# sbus-ppm.net
KiCad netlist of a schematic drawn in EAGLE
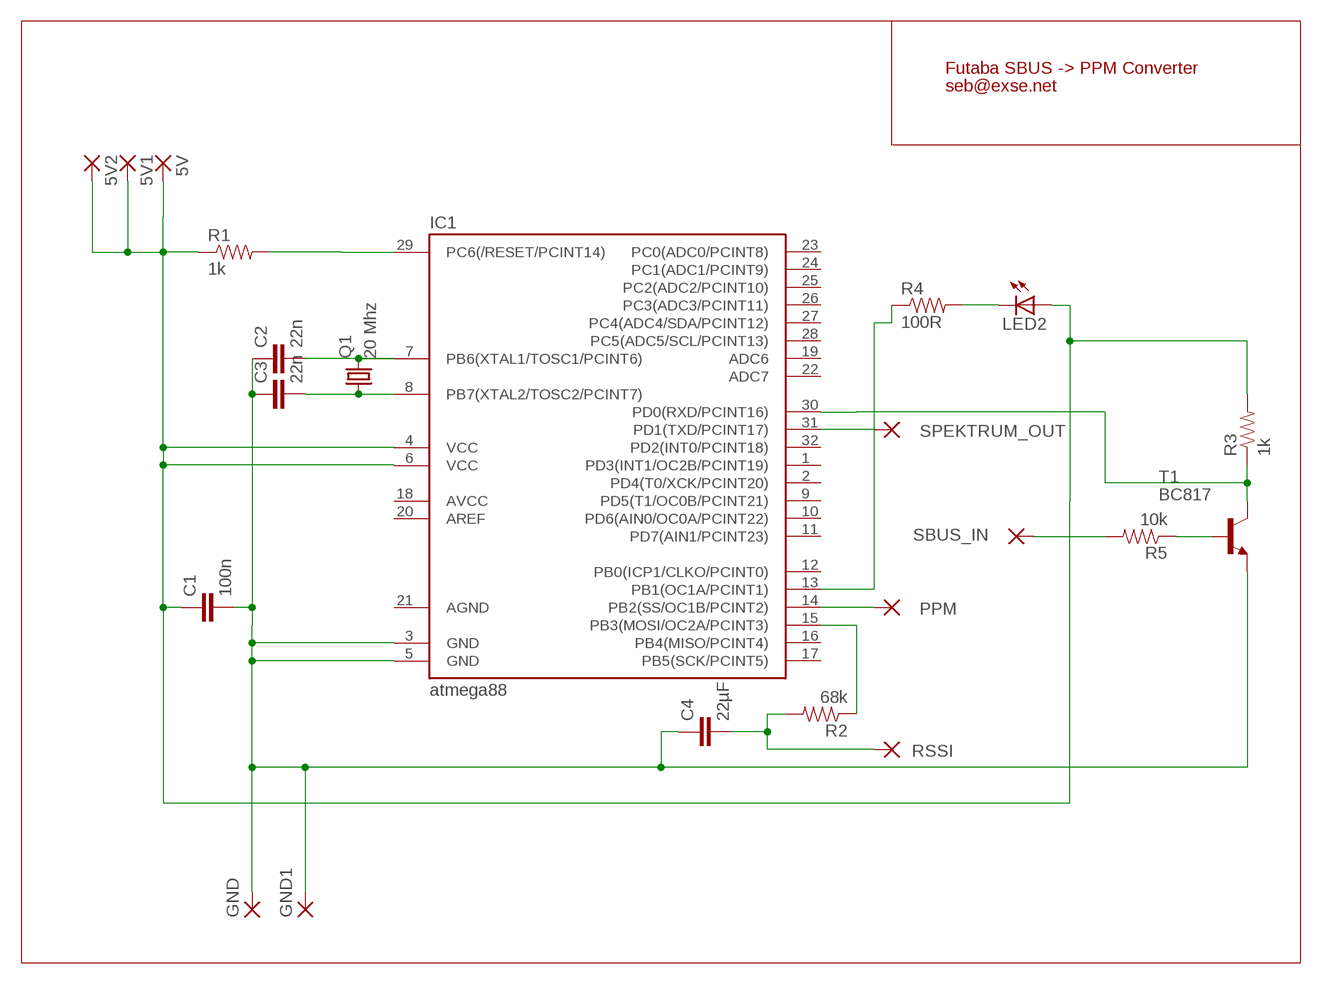
[diagram p0: schematic, sheet 1]

(export (version "E")
  (design (tool "Eeschema 10.0.6"))
  (components
    (comp (ref "5V")
      (value "SMD2")
      (footprint "eagle-import:SMD1,27-2,54")
      (libsource (lib "eagle-import") (part "SMD2"))
    )
    (comp (ref "5V1")
      (value "SMD2")
      (footprint "eagle-import:SMD1,27-2,54")
      (libsource (lib "eagle-import") (part "SMD2"))
    )
    (comp (ref "5V2")
      (value "SMD2")
      (footprint "eagle-import:SMD1,27-2,54")
      (libsource (lib "eagle-import") (part "SMD2"))
    )
    (comp (ref "C1")
      (value "100n")
      (footprint "eagle-import:0805")
      (libsource (lib "eagle-import") (part "CAP0805"))
    )
    (comp (ref "C2")
      (value "22n")
      (footprint "eagle-import:0805")
      (libsource (lib "eagle-import") (part "CAP0805"))
    )
    (comp (ref "C3")
      (value "22n")
      (footprint "eagle-import:0805")
      (libsource (lib "eagle-import") (part "CAP0805"))
    )
    (comp (ref "C4")
      (value "22µF")
      (footprint "eagle-import:0805")
      (libsource (lib "eagle-import") (part "CAP0805"))
    )
    (comp (ref "GND")
      (value "SMD2")
      (footprint "eagle-import:SMD1,27-2,54")
      (libsource (lib "eagle-import") (part "SMD2"))
    )
    (comp (ref "GND1")
      (value "SMD2")
      (footprint "eagle-import:SMD1,27-2,54")
      (libsource (lib "eagle-import") (part "SMD2"))
    )
    (comp (ref "IC1")
      (value "atmega88")
      (footprint "eagle-import:TQFP32-08")
      (libsource (lib "eagle-import") (part "MEGA48/88/168-AU"))
    )
    (comp (ref "LED2")
      (value "LEDCHIPLED_0805")
      (footprint "eagle-import:CHIPLED_0805")
      (libsource (lib "eagle-import") (part "LEDCHIPLED_0805"))
    )
    (comp (ref "PPM")
      (value "SMD2")
      (footprint "eagle-import:SMD1,27-2,54")
      (libsource (lib "eagle-import") (part "SMD2"))
    )
    (comp (ref "Q1")
      (value "20 Mhz")
      (footprint "eagle-import:X22")
      (libsource (lib "eagle-import") (part "X22-OSCILLATOR"))
    )
    (comp (ref "R1")
      (value "1k")
      (footprint "eagle-import:0805")
      (libsource (lib "eagle-import") (part "RESISTOR"))
    )
    (comp (ref "R2")
      (value "68k")
      (footprint "eagle-import:0805")
      (libsource (lib "eagle-import") (part "RESISTOR"))
    )
    (comp (ref "R3")
      (value "1k")
      (footprint "eagle-import:0805")
      (libsource (lib "eagle-import") (part "RESISTOR"))
    )
    (comp (ref "R4")
      (value "100R")
      (footprint "eagle-import:0805")
      (libsource (lib "eagle-import") (part "RESISTOR"))
    )
    (comp (ref "R5")
      (value "10k")
      (footprint "eagle-import:0805")
      (libsource (lib "eagle-import") (part "RESISTOR"))
    )
    (comp (ref "RSSI")
      (value "SMD2")
      (footprint "eagle-import:SMD1,27-2,54")
      (libsource (lib "eagle-import") (part "SMD2"))
    )
    (comp (ref "SBUS_IN")
      (value "SMD2")
      (footprint "eagle-import:SMD1,27-2,54")
      (libsource (lib "eagle-import") (part "SMD2"))
    )
    (comp (ref "SPEKTRUM_OUT")
      (value "SMD2")
      (footprint "eagle-import:SMD1,27-2,54")
      (libsource (lib "eagle-import") (part "SMD2"))
    )
    (comp (ref "T1")
      (value "BC817")
      (footprint "eagle-import:SOT23")
      (libsource (lib "eagle-import") (part "BC847"))
    )
  )
  (nets
    (net (code "1") (name "/AGND") (class "Default")
      (node (ref "IC1") (pin "21") (pinfunction "AGND_21") (pintype "power_in"))
    )
    (net (code "2") (name "Net-(5V-P)") (class "Default")
      (node (ref "5V") (pin "1") (pinfunction "P_1") (pintype "passive"))
      (node (ref "5V1") (pin "1") (pinfunction "P_1") (pintype "passive"))
      (node (ref "5V2") (pin "1") (pinfunction "P_1") (pintype "passive"))
      (node (ref "C1") (pin "1") (pinfunction "1_1") (pintype "passive"))
      (node (ref "IC1") (pin "4") (pinfunction "VCC_4") (pintype "power_in"))
      (node (ref "IC1") (pin "6") (pinfunction "VCC_6") (pintype "power_in"))
      (node (ref "LED2") (pin "A") (pinfunction "A_A") (pintype "passive"))
      (node (ref "R1") (pin "1") (pinfunction "1_1") (pintype "passive"))
      (node (ref "R3") (pin "2") (pinfunction "2_2") (pintype "passive"))
    )
    (net (code "3") (name "Net-(GND-P)") (class "Default")
      (node (ref "C1") (pin "2") (pinfunction "2_2") (pintype "passive"))
      (node (ref "C2") (pin "1") (pinfunction "1_1") (pintype "passive"))
      (node (ref "C3") (pin "1") (pinfunction "1_1") (pintype "passive"))
      (node (ref "C4") (pin "1") (pinfunction "1_1") (pintype "passive"))
      (node (ref "GND") (pin "1") (pinfunction "P_1") (pintype "passive"))
      (node (ref "GND1") (pin "1") (pinfunction "P_1") (pintype "passive"))
      (node (ref "IC1") (pin "3") (pinfunction "GND_3") (pintype "power_in"))
      (node (ref "IC1") (pin "5") (pinfunction "GND_5") (pintype "power_in"))
      (node (ref "T1") (pin "2") (pinfunction "E_2") (pintype "passive"))
    )
    (net (code "4") (name "Net-(IC1-PB1(OC1A{slash}PCINT1))") (class "Default")
      (node (ref "IC1") (pin "13") (pinfunction "PB1(OC1A/PCINT1)_13") (pintype "bidirectional"))
      (node (ref "R4") (pin "1") (pinfunction "1_1") (pintype "passive"))
    )
    (net (code "5") (name "Net-(IC1-PB2(SS{slash}OC1B{slash}PCINT2))") (class "Default")
      (node (ref "IC1") (pin "14") (pinfunction "PB2(SS/OC1B/PCINT2)_14") (pintype "bidirectional"))
      (node (ref "PPM") (pin "1") (pinfunction "P_1") (pintype "passive"))
    )
    (net (code "6") (name "Net-(IC1-PB3(MOSI{slash}OC2A{slash}PCINT3))") (class "Default")
      (node (ref "IC1") (pin "15") (pinfunction "PB3(MOSI/OC2A/PCINT3)_15") (pintype "bidirectional"))
      (node (ref "R2") (pin "1") (pinfunction "1_1") (pintype "passive"))
    )
    (net (code "7") (name "Net-(IC1-PB6(XTAL1{slash}TOSC1{slash}PCINT6))") (class "Default")
      (node (ref "C2") (pin "2") (pinfunction "2_2") (pintype "passive"))
      (node (ref "IC1") (pin "7") (pinfunction "PB6(XTAL1/TOSC1/PCINT6)_7") (pintype "bidirectional"))
      (node (ref "Q1") (pin "3") (pinfunction "2_3") (pintype "passive"))
    )
    (net (code "8") (name "Net-(IC1-PB7(XTAL2{slash}TOSC2{slash}PCINT7))") (class "Default")
      (node (ref "C3") (pin "2") (pinfunction "2_2") (pintype "passive"))
      (node (ref "IC1") (pin "8") (pinfunction "PB7(XTAL2/TOSC2/PCINT7)_8") (pintype "bidirectional"))
      (node (ref "Q1") (pin "1") (pinfunction "1_1") (pintype "passive"))
    )
    (net (code "9") (name "Net-(IC1-PC6({slash}RESET{slash}PCINT14))") (class "Default")
      (node (ref "IC1") (pin "29") (pinfunction "PC6(/RESET/PCINT14)_29") (pintype "bidirectional"))
      (node (ref "R1") (pin "2") (pinfunction "2_2") (pintype "passive"))
    )
    (net (code "10") (name "Net-(IC1-PD0(RXD{slash}PCINT16))") (class "Default")
      (node (ref "IC1") (pin "30") (pinfunction "PD0(RXD/PCINT16)_30") (pintype "bidirectional"))
      (node (ref "R3") (pin "1") (pinfunction "1_1") (pintype "passive"))
      (node (ref "T1") (pin "3") (pinfunction "C_3") (pintype "passive"))
    )
    (net (code "11") (name "Net-(IC1-PD1(TXD{slash}PCINT17))") (class "Default")
      (node (ref "IC1") (pin "31") (pinfunction "PD1(TXD/PCINT17)_31") (pintype "bidirectional"))
      (node (ref "SPEKTRUM_OUT") (pin "1") (pinfunction "P_1") (pintype "passive"))
    )
    (net (code "12") (name "Net-(LED2-PadC)") (class "Default")
      (node (ref "LED2") (pin "C") (pinfunction "C_C") (pintype "passive"))
      (node (ref "R4") (pin "2") (pinfunction "2_2") (pintype "passive"))
    )
    (net (code "13") (name "Net-(RSSI-P)") (class "Default")
      (node (ref "C4") (pin "2") (pinfunction "2_2") (pintype "passive"))
      (node (ref "R2") (pin "2") (pinfunction "2_2") (pintype "passive"))
      (node (ref "RSSI") (pin "1") (pinfunction "P_1") (pintype "passive"))
    )
    (net (code "14") (name "Net-(SBUS_IN-P)") (class "Default")
      (node (ref "R5") (pin "2") (pinfunction "2_2") (pintype "passive"))
      (node (ref "SBUS_IN") (pin "1") (pinfunction "P_1") (pintype "passive"))
    )
    (net (code "15") (name "Net-(T1-B)") (class "Default")
      (node (ref "R5") (pin "1") (pinfunction "1_1") (pintype "passive"))
      (node (ref "T1") (pin "1") (pinfunction "B_1") (pintype "passive"))
    )
    (net (code "16") (name "unconnected-(IC1-ADC6-Pad19)") (class "Default")
      (node (ref "IC1") (pin "19") (pinfunction "ADC6_19") (pintype "passive"))
    )
    (net (code "17") (name "unconnected-(IC1-ADC7-Pad22)") (class "Default")
      (node (ref "IC1") (pin "22") (pinfunction "ADC7_22") (pintype "passive"))
    )
    (net (code "18") (name "unconnected-(IC1-AREF-Pad20)") (class "Default")
      (node (ref "IC1") (pin "20") (pinfunction "AREF_20") (pintype "passive"))
    )
    (net (code "19") (name "unconnected-(IC1-AVCC-Pad18)") (class "Default")
      (node (ref "IC1") (pin "18") (pinfunction "AVCC_18") (pintype "passive"))
    )
    (net (code "20") (name "unconnected-(IC1-PB0(ICP1{slash}CLKO{slash}PCINT0)-Pad12)") (class "Default")
      (node (ref "IC1") (pin "12") (pinfunction "PB0(ICP1/CLKO/PCINT0)_12") (pintype "bidirectional"))
    )
    (net (code "21") (name "unconnected-(IC1-PB4(MISO{slash}PCINT4)-Pad16)") (class "Default")
      (node (ref "IC1") (pin "16") (pinfunction "PB4(MISO/PCINT4)_16") (pintype "bidirectional"))
    )
    (net (code "22") (name "unconnected-(IC1-PB5(SCK{slash}PCINT5)-Pad17)") (class "Default")
      (node (ref "IC1") (pin "17") (pinfunction "PB5(SCK/PCINT5)_17") (pintype "bidirectional"))
    )
    (net (code "23") (name "unconnected-(IC1-PC0(ADC0{slash}PCINT8)-Pad23)") (class "Default")
      (node (ref "IC1") (pin "23") (pinfunction "PC0(ADC0/PCINT8)_23") (pintype "bidirectional"))
    )
    (net (code "24") (name "unconnected-(IC1-PC1(ADC1{slash}PCINT9)-Pad24)") (class "Default")
      (node (ref "IC1") (pin "24") (pinfunction "PC1(ADC1/PCINT9)_24") (pintype "bidirectional"))
    )
    (net (code "25") (name "unconnected-(IC1-PC2(ADC2{slash}PCINT10)-Pad25)") (class "Default")
      (node (ref "IC1") (pin "25") (pinfunction "PC2(ADC2/PCINT10)_25") (pintype "bidirectional"))
    )
    (net (code "26") (name "unconnected-(IC1-PC3(ADC3{slash}PCINT11)-Pad26)") (class "Default")
      (node (ref "IC1") (pin "26") (pinfunction "PC3(ADC3/PCINT11)_26") (pintype "bidirectional"))
    )
    (net (code "27") (name "unconnected-(IC1-PC4(ADC4{slash}SDA{slash}PCINT12)-Pad27)") (class "Default")
      (node (ref "IC1") (pin "27") (pinfunction "PC4(ADC4/SDA/PCINT12)_27") (pintype "bidirectional"))
    )
    (net (code "28") (name "unconnected-(IC1-PC5(ADC5{slash}SCL{slash}PCINT13)-Pad28)") (class "Default")
      (node (ref "IC1") (pin "28") (pinfunction "PC5(ADC5/SCL/PCINT13)_28") (pintype "bidirectional"))
    )
    (net (code "29") (name "unconnected-(IC1-PD2(INT0{slash}PCINT18)-Pad32)") (class "Default")
      (node (ref "IC1") (pin "32") (pinfunction "PD2(INT0/PCINT18)_32") (pintype "bidirectional"))
    )
    (net (code "30") (name "unconnected-(IC1-PD3(INT1{slash}OC2B{slash}PCINT19)-Pad1)") (class "Default")
      (node (ref "IC1") (pin "1") (pinfunction "PD3(INT1/OC2B/PCINT19)_1") (pintype "bidirectional"))
    )
    (net (code "31") (name "unconnected-(IC1-PD4(T0{slash}XCK{slash}PCINT20)-Pad2)") (class "Default")
      (node (ref "IC1") (pin "2") (pinfunction "PD4(T0/XCK/PCINT20)_2") (pintype "bidirectional"))
    )
    (net (code "32") (name "unconnected-(IC1-PD5(T1{slash}OC0B{slash}PCINT21)-Pad9)") (class "Default")
      (node (ref "IC1") (pin "9") (pinfunction "PD5(T1/OC0B/PCINT21)_9") (pintype "bidirectional"))
    )
    (net (code "33") (name "unconnected-(IC1-PD6(AIN0{slash}OC0A{slash}PCINT22)-Pad10)") (class "Default")
      (node (ref "IC1") (pin "10") (pinfunction "PD6(AIN0/OC0A/PCINT22)_10") (pintype "bidirectional"))
    )
    (net (code "34") (name "unconnected-(IC1-PD7(AIN1{slash}PCINT23)-Pad11)") (class "Default")
      (node (ref "IC1") (pin "11") (pinfunction "PD7(AIN1/PCINT23)_11") (pintype "bidirectional"))
    )
  )
)
